# wifibasestation-tssop.net
KiCad netlist of a schematic drawn in EAGLE
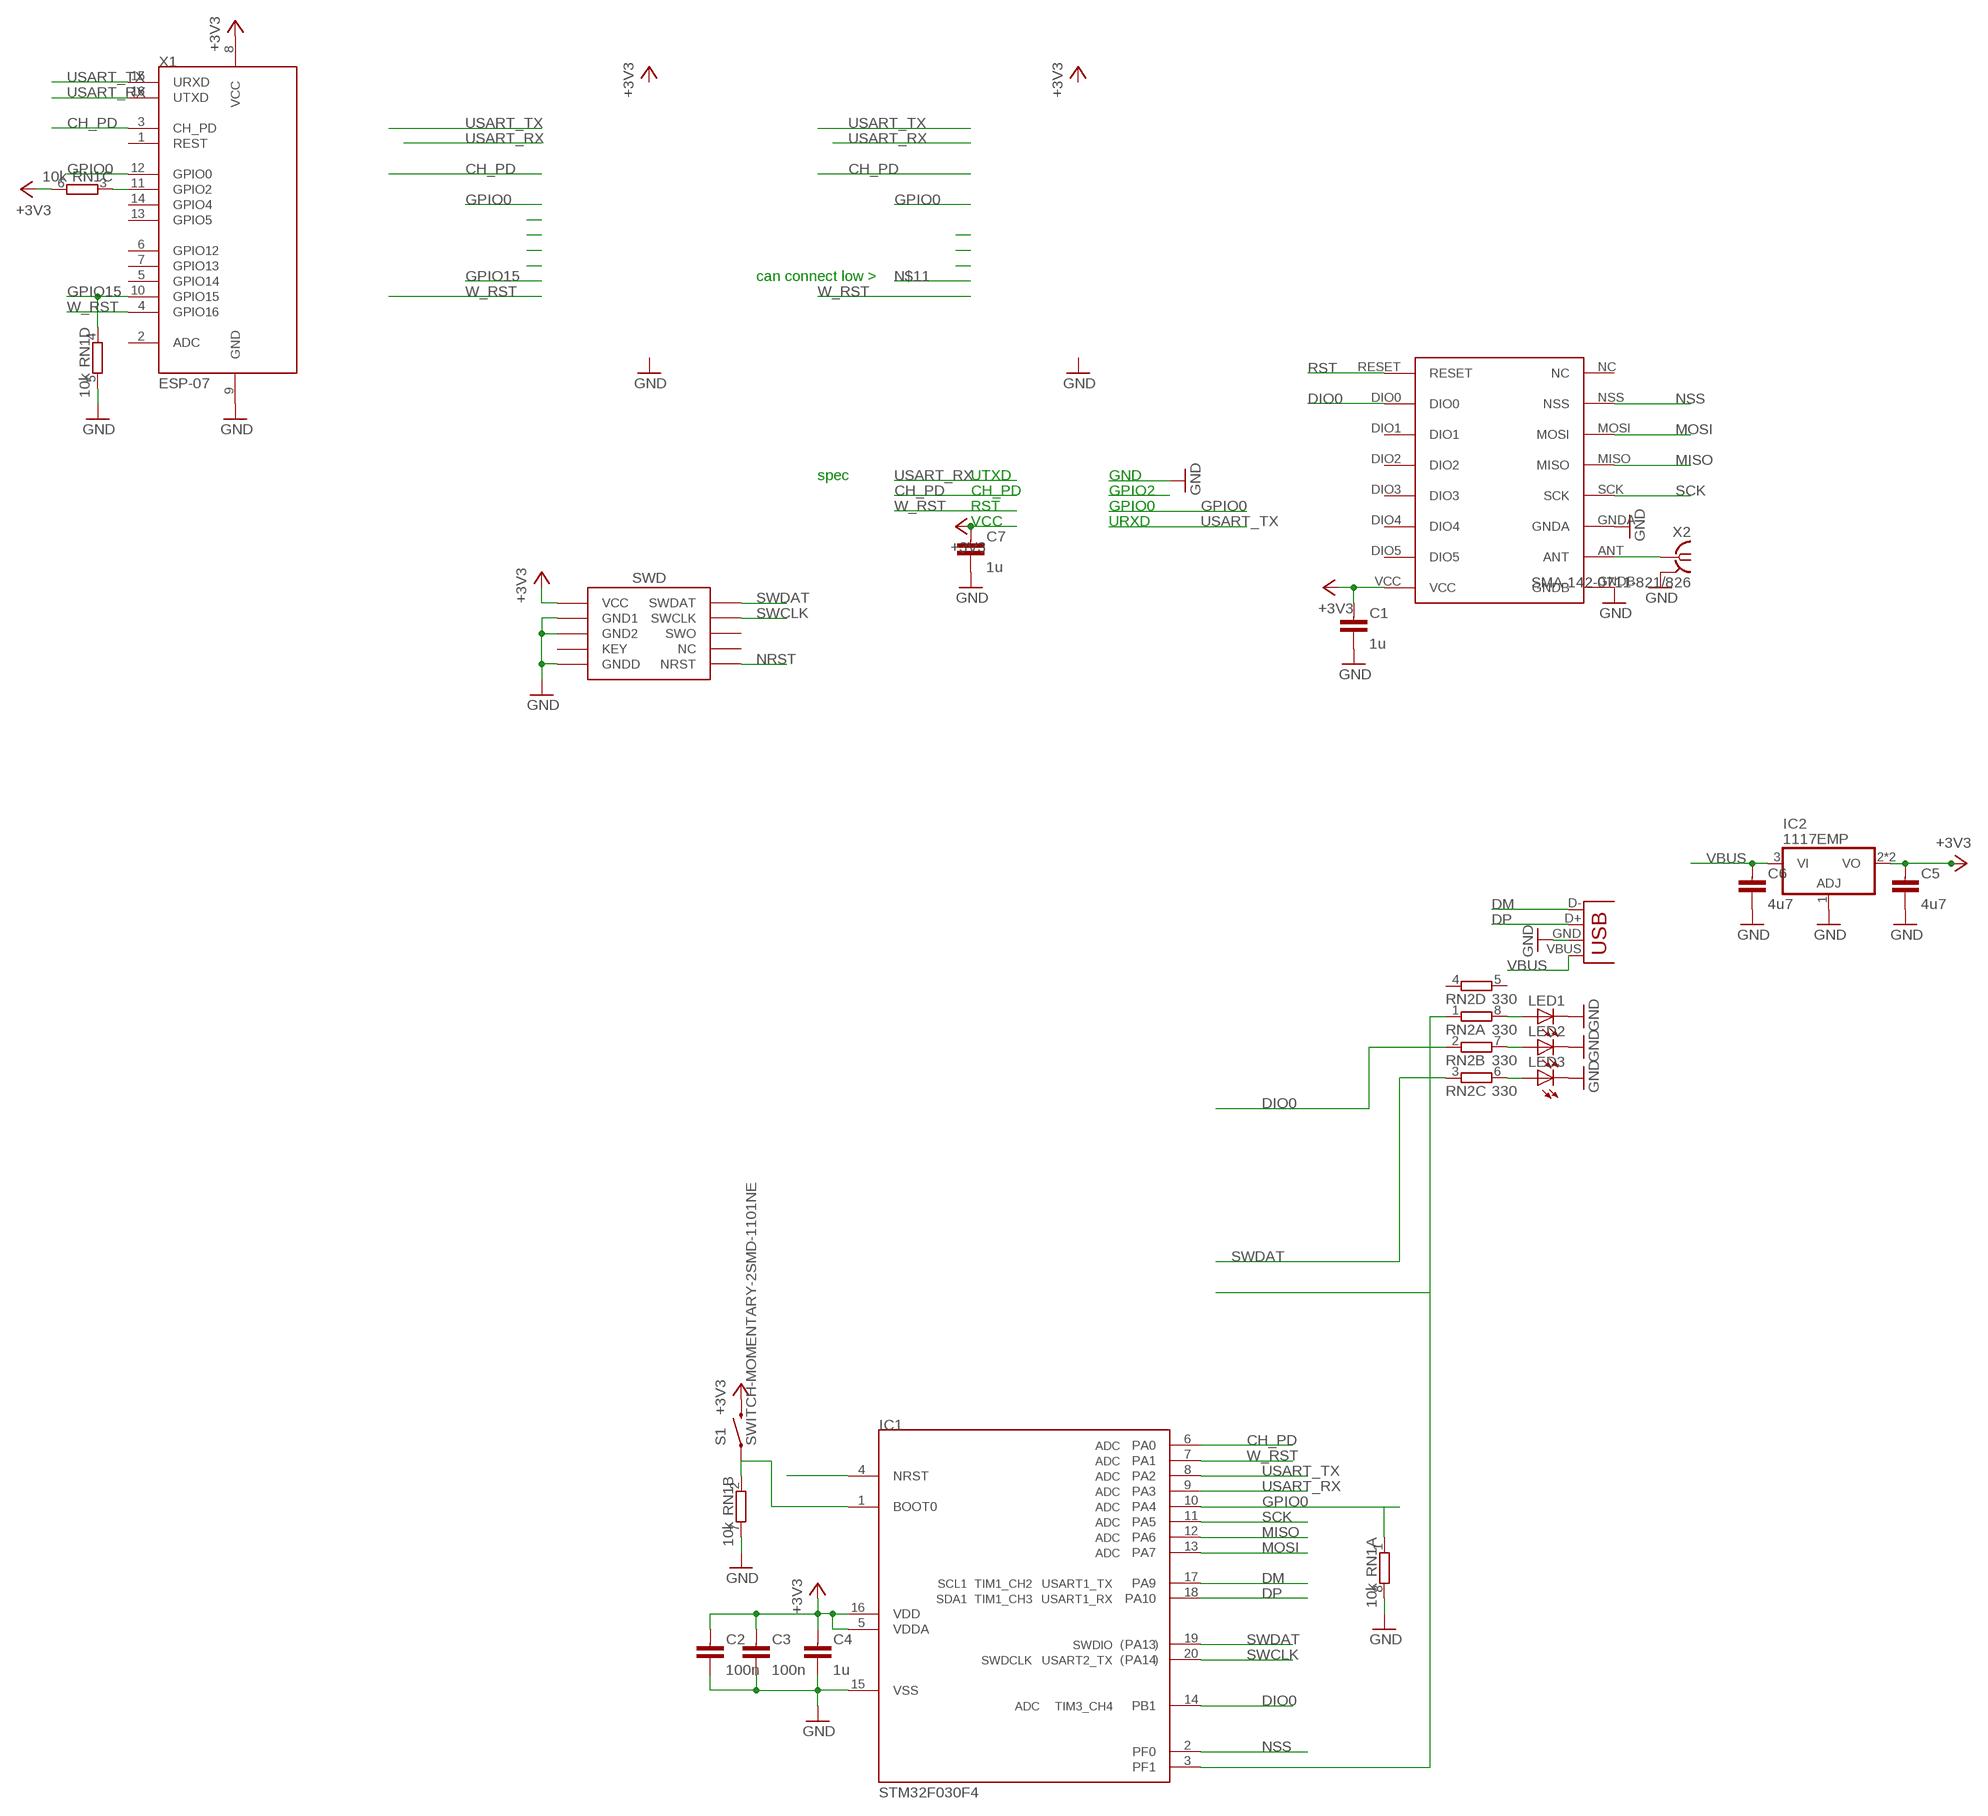
[diagram p0: schematic, sheet 1]

(export (version "E")
  (design (tool "Eeschema 10.0.6"))
  (components
    (comp (ref "C1")
      (value "1u")
      (footprint "eagle-import:C0603-N")
      (libsource (lib "eagle-import") (part "CAPACITOR0603-N"))
    )
    (comp (ref "C2")
      (value "100n")
      (footprint "eagle-import:C0603-N")
      (libsource (lib "eagle-import") (part "CAPACITOR0603-N"))
    )
    (comp (ref "C3")
      (value "100n")
      (footprint "eagle-import:C0603-N")
      (libsource (lib "eagle-import") (part "CAPACITOR0603-N"))
    )
    (comp (ref "C4")
      (value "1u")
      (footprint "eagle-import:C0603-N")
      (libsource (lib "eagle-import") (part "CAPACITOR0603-N"))
    )
    (comp (ref "C5")
      (value "4u7")
      (footprint "eagle-import:C0805-N")
      (libsource (lib "eagle-import") (part "CAPACITOR0805-N"))
    )
    (comp (ref "C6")
      (value "4u7")
      (footprint "eagle-import:C0603-N")
      (libsource (lib "eagle-import") (part "CAPACITOR0603-N"))
    )
    (comp (ref "C7")
      (value "1u")
      (footprint "eagle-import:C0603-N")
      (libsource (lib "eagle-import") (part "CAPACITOR0603-N"))
    )
    (comp (ref "IC1")
      (value "STM32F030F4")
      (footprint "eagle-import:TSSOP20")
      (libsource (lib "eagle-import") (part "STM32F030F4"))
    )
    (comp (ref "IC2")
      (value "1117EMP")
      (footprint "eagle-import:SOT223")
      (libsource (lib "eagle-import") (part "1117EMP"))
    )
    (comp (ref "J1")
      (value "SWD_SHROUD_SMD")
      (footprint "eagle-import:SWD_SMD_SHROUD")
      (libsource (lib "eagle-import") (part "SWD_SHROUD_SMD"))
    )
    (comp (ref "JP1")
      (value "USB-A-H")
      (footprint "eagle-import:USB-A-H")
      (libsource (lib "eagle-import") (part "USB-A-H"))
    )
    (comp (ref "LED1")
      (value "LEDCHIP-LED0805")
      (footprint "eagle-import:CHIP-LED0805")
      (libsource (lib "eagle-import") (part "LEDCHIP-LED0805"))
    )
    (comp (ref "LED2")
      (value "LEDCHIP-LED0805")
      (footprint "eagle-import:CHIP-LED0805")
      (libsource (lib "eagle-import") (part "LEDCHIP-LED0805"))
    )
    (comp (ref "LED3")
      (value "LEDCHIP-LED0805")
      (footprint "eagle-import:CHIP-LED0805")
      (libsource (lib "eagle-import") (part "LEDCHIP-LED0805"))
    )
    (comp (ref "RN1")
      (value "10k")
      (footprint "eagle-import:EXB38V")
      (libsource (lib "eagle-import") (part "4R-NEXB38V"))
    )
    (comp (ref "RN2")
      (value "330")
      (footprint "eagle-import:EXB38V")
      (libsource (lib "eagle-import") (part "4R-NEXB38V"))
    )
    (comp (ref "S1")
      (value "SWITCH-MOMENTARY-2SMD-1101NE")
      (footprint "eagle-import:TACTILE-SWITCH-1101NE")
      (libsource (lib "eagle-import") (part "SWITCH-MOMENTARY-2SMD-1101NE"))
    )
    (comp (ref "U$1")
      (value "RFM69HW")
      (footprint "eagle-import:RFM")
      (libsource (lib "eagle-import") (part "RFM69HW"))
    )
    (comp (ref "X1")
      (value "ESP-07")
      (footprint "eagle-import:ESP-07")
      (libsource (lib "eagle-import") (part "ESP-07"))
    )
    (comp (ref "X2")
      (value "SMA-142-0711-821/826")
      (footprint "eagle-import:J502-ND-142-0711-821_826")
      (fields (field (name "MF") "JOHNSON COMPONENTS") (field (name "MPN") "142-0711-821"))
      (libsource (lib "eagle-import") (part "SMA-142-0711-821/826"))
    )
  )
  (nets
    (net (code "1") (name "+3V3") (class "Default")
      (node (ref "C1") (pin "1") (pinfunction "1_1") (pintype "passive"))
      (node (ref "C2") (pin "1") (pinfunction "1_1") (pintype "passive"))
      (node (ref "C3") (pin "1") (pinfunction "1_1") (pintype "passive"))
      (node (ref "C4") (pin "1") (pinfunction "1_1") (pintype "passive"))
      (node (ref "C5") (pin "1") (pinfunction "1_1") (pintype "passive"))
      (node (ref "C7") (pin "1") (pinfunction "1_1") (pintype "passive"))
      (node (ref "IC1") (pin "16") (pinfunction "VDD_16") (pintype "power_in"))
      (node (ref "IC1") (pin "5") (pinfunction "VDDA_5") (pintype "power_in"))
      (node (ref "IC2") (pin "2") (pinfunction "VO_2") (pintype "passive"))
      (node (ref "IC2") (pin "4") (pinfunction "VO_4") (pintype "passive"))
      (node (ref "J1") (pin "1") (pinfunction "VCC_1") (pintype "power_in"))
      (node (ref "RN1") (pin "6") (pinfunction "2_6") (pintype "passive"))
      (node (ref "S1") (pin "2") (pinfunction "2_2") (pintype "passive"))
      (node (ref "U$1") (pin "VCC") (pinfunction "VCC_VCC") (pintype "bidirectional"))
      (node (ref "X1") (pin "8") (pinfunction "VCC_8") (pintype "power_in"))
    )
    (net (code "2") (name "/CH_PD") (class "Default")
      (node (ref "IC1") (pin "6") (pinfunction "PA0_6") (pintype "bidirectional"))
      (node (ref "X1") (pin "3") (pinfunction "CH_PD_3") (pintype "input"))
    )
    (net (code "3") (name "/DIO0") (class "Default")
      (node (ref "IC1") (pin "14") (pinfunction "PB1_14") (pintype "bidirectional"))
      (node (ref "RN2") (pin "2") (pinfunction "1_2") (pintype "passive"))
      (node (ref "U$1") (pin "DIO0") (pinfunction "DIO0_DIO0") (pintype "bidirectional"))
    )
    (net (code "4") (name "/DM") (class "Default")
      (node (ref "IC1") (pin "17") (pinfunction "PA9_17") (pintype "bidirectional"))
      (node (ref "JP1") (pin "D-") (pinfunction "D+_D-") (pintype "bidirectional"))
    )
    (net (code "5") (name "/DP") (class "Default")
      (node (ref "IC1") (pin "18") (pinfunction "PA10_18") (pintype "bidirectional"))
      (node (ref "JP1") (pin "D+") (pinfunction "D-_D+") (pintype "bidirectional"))
    )
    (net (code "6") (name "/GPIO0") (class "Default")
      (node (ref "IC1") (pin "10") (pinfunction "PA4_10") (pintype "bidirectional"))
      (node (ref "RN1") (pin "1") (pinfunction "1_1") (pintype "passive"))
      (node (ref "X1") (pin "12") (pinfunction "GPIO0_12") (pintype "bidirectional"))
    )
    (net (code "7") (name "/GPIO15") (class "Default")
      (node (ref "RN1") (pin "4") (pinfunction "1_4") (pintype "passive"))
      (node (ref "X1") (pin "10") (pinfunction "GPIO15_10") (pintype "bidirectional"))
    )
    (net (code "8") (name "/MISO") (class "Default")
      (node (ref "IC1") (pin "12") (pinfunction "PA6_12") (pintype "bidirectional"))
      (node (ref "U$1") (pin "MISO") (pinfunction "MISO_MISO") (pintype "bidirectional"))
    )
    (net (code "9") (name "/MOSI") (class "Default")
      (node (ref "IC1") (pin "13") (pinfunction "PA7_13") (pintype "bidirectional"))
      (node (ref "U$1") (pin "MOSI") (pinfunction "MOSI_MOSI") (pintype "bidirectional"))
    )
    (net (code "14") (name "/NRST") (class "Default")
      (node (ref "IC1") (pin "4") (pinfunction "NRST_4") (pintype "input"))
      (node (ref "J1") (pin "10") (pinfunction "NRST_10") (pintype "bidirectional"))
    )
    (net (code "15") (name "/NSS") (class "Default")
      (node (ref "IC1") (pin "2") (pinfunction "PF0_2") (pintype "bidirectional"))
      (node (ref "U$1") (pin "NSS") (pinfunction "NSS_NSS") (pintype "bidirectional"))
    )
    (net (code "16") (name "/RST") (class "Default")
      (node (ref "U$1") (pin "RESET") (pinfunction "RESET_RESET") (pintype "bidirectional"))
    )
    (net (code "17") (name "/SCK") (class "Default")
      (node (ref "IC1") (pin "11") (pinfunction "PA5_11") (pintype "bidirectional"))
      (node (ref "U$1") (pin "SCK") (pinfunction "SCK_SCK") (pintype "bidirectional"))
    )
    (net (code "18") (name "/SWCLK") (class "Default")
      (node (ref "IC1") (pin "20") (pinfunction "PA14_20") (pintype "bidirectional"))
      (node (ref "J1") (pin "4") (pinfunction "SWCLK_4") (pintype "bidirectional"))
    )
    (net (code "19") (name "/SWDAT") (class "Default")
      (node (ref "IC1") (pin "19") (pinfunction "PA13_19") (pintype "bidirectional"))
      (node (ref "J1") (pin "2") (pinfunction "SWDAT_2") (pintype "bidirectional"))
      (node (ref "RN2") (pin "3") (pinfunction "1_3") (pintype "passive"))
    )
    (net (code "20") (name "/USART_RX") (class "Default")
      (node (ref "IC1") (pin "9") (pinfunction "PA3_9") (pintype "bidirectional"))
      (node (ref "X1") (pin "16") (pinfunction "UTXD_16") (pintype "output"))
    )
    (net (code "21") (name "/USART_TX") (class "Default")
      (node (ref "IC1") (pin "8") (pinfunction "PA2_8") (pintype "bidirectional"))
      (node (ref "X1") (pin "15") (pinfunction "URXD_15") (pintype "input"))
    )
    (net (code "22") (name "/VBUS") (class "Default")
      (node (ref "C6") (pin "1") (pinfunction "1_1") (pintype "passive"))
      (node (ref "IC2") (pin "3") (pinfunction "VI_3") (pintype "input"))
      (node (ref "JP1") (pin "VBUS") (pinfunction "GND_VBUS") (pintype "bidirectional"))
    )
    (net (code "23") (name "/W_RST") (class "Default")
      (node (ref "IC1") (pin "7") (pinfunction "PA1_7") (pintype "bidirectional"))
      (node (ref "X1") (pin "4") (pinfunction "GPIO16_4") (pintype "bidirectional"))
    )
    (net (code "24") (name "GND") (class "Default")
      (node (ref "C1") (pin "2") (pinfunction "2_2") (pintype "passive"))
      (node (ref "C2") (pin "2") (pinfunction "2_2") (pintype "passive"))
      (node (ref "C3") (pin "2") (pinfunction "2_2") (pintype "passive"))
      (node (ref "C4") (pin "2") (pinfunction "2_2") (pintype "passive"))
      (node (ref "C5") (pin "2") (pinfunction "2_2") (pintype "passive"))
      (node (ref "C6") (pin "2") (pinfunction "2_2") (pintype "passive"))
      (node (ref "C7") (pin "2") (pinfunction "2_2") (pintype "passive"))
      (node (ref "IC1") (pin "15") (pinfunction "VSS_15") (pintype "power_in"))
      (node (ref "IC2") (pin "1") (pinfunction "ADJ_1") (pintype "input"))
      (node (ref "J1") (pin "3") (pinfunction "GND1_3") (pintype "power_in"))
      (node (ref "J1") (pin "5") (pinfunction "GND2_5") (pintype "power_in"))
      (node (ref "J1") (pin "9") (pinfunction "GNDD_9") (pintype "power_in"))
      (node (ref "JP1") (pin "GND") (pinfunction "VBUS_GND") (pintype "bidirectional"))
      (node (ref "LED1") (pin "C") (pinfunction "C_C") (pintype "passive"))
      (node (ref "LED2") (pin "C") (pinfunction "C_C") (pintype "passive"))
      (node (ref "LED3") (pin "C") (pinfunction "C_C") (pintype "passive"))
      (node (ref "RN1") (pin "5") (pinfunction "2_5") (pintype "passive"))
      (node (ref "RN1") (pin "7") (pinfunction "2_7") (pintype "passive"))
      (node (ref "RN1") (pin "8") (pinfunction "2_8") (pintype "passive"))
      (node (ref "U$1") (pin "GNDA") (pinfunction "GNDA_GNDA") (pintype "bidirectional"))
      (node (ref "U$1") (pin "GNDB") (pinfunction "GNDB_GNDB") (pintype "bidirectional"))
      (node (ref "X1") (pin "9") (pinfunction "GND_9") (pintype "power_in"))
      (node (ref "X2") (pin "G@1") (pinfunction "2_G@1") (pintype "passive"))
      (node (ref "X2") (pin "G@2") (pinfunction "2_G@2") (pintype "passive"))
      (node (ref "X2") (pin "G@3") (pinfunction "2_G@3") (pintype "passive"))
      (node (ref "X2") (pin "G@4") (pinfunction "2_G@4") (pintype "passive"))
    )
    (net (code "25") (name "Net-(IC1-BOOT0)") (class "Default")
      (node (ref "IC1") (pin "1") (pinfunction "BOOT0_1") (pintype "input"))
      (node (ref "RN1") (pin "2") (pinfunction "1_2") (pintype "passive"))
      (node (ref "S1") (pin "1") (pinfunction "1_1") (pintype "passive"))
    )
    (net (code "26") (name "Net-(IC1-PF1)") (class "Default")
      (node (ref "IC1") (pin "3") (pinfunction "PF1_3") (pintype "bidirectional"))
      (node (ref "RN2") (pin "1") (pinfunction "1_1") (pintype "passive"))
    )
    (net (code "27") (name "Net-(RN1C-1)") (class "Default")
      (node (ref "RN1") (pin "3") (pinfunction "1_3") (pintype "passive"))
      (node (ref "X1") (pin "11") (pinfunction "GPIO2_11") (pintype "bidirectional"))
    )
    (net (code "28") (name "Net-(RN2A-2)") (class "Default")
      (node (ref "LED1") (pin "A") (pinfunction "A_A") (pintype "passive"))
      (node (ref "RN2") (pin "8") (pinfunction "2_8") (pintype "passive"))
    )
    (net (code "29") (name "Net-(RN2B-2)") (class "Default")
      (node (ref "LED2") (pin "A") (pinfunction "A_A") (pintype "passive"))
      (node (ref "RN2") (pin "7") (pinfunction "2_7") (pintype "passive"))
    )
    (net (code "30") (name "Net-(RN2C-2)") (class "Default")
      (node (ref "LED3") (pin "A") (pinfunction "A_A") (pintype "passive"))
      (node (ref "RN2") (pin "6") (pinfunction "2_6") (pintype "passive"))
    )
    (net (code "31") (name "Net-(U$1-PadANT)") (class "Default")
      (node (ref "U$1") (pin "ANT") (pinfunction "ANT_ANT") (pintype "bidirectional"))
      (node (ref "X2") (pin "1") (pinfunction "1_1") (pintype "passive"))
    )
    (net (code "32") (name "unconnected-(J1-KEY-Pad7)") (class "Default")
      (node (ref "J1") (pin "7") (pinfunction "KEY_7") (pintype "bidirectional"))
    )
    (net (code "33") (name "unconnected-(J1-NC-Pad8)") (class "Default")
      (node (ref "J1") (pin "8") (pinfunction "NC_8") (pintype "no_connect"))
    )
    (net (code "34") (name "unconnected-(J1-SWO-Pad6)") (class "Default")
      (node (ref "J1") (pin "6") (pinfunction "SWO_6") (pintype "bidirectional"))
    )
    (net (code "35") (name "unconnected-(RN2D-1-Pad4)") (class "Default")
      (node (ref "RN2") (pin "4") (pinfunction "1_4") (pintype "passive"))
    )
    (net (code "36") (name "unconnected-(RN2D-2-Pad5)") (class "Default")
      (node (ref "RN2") (pin "5") (pinfunction "2_5") (pintype "passive"))
    )
    (net (code "37") (name "unconnected-(U$1-PadDIO1)") (class "Default")
      (node (ref "U$1") (pin "DIO1") (pinfunction "DIO1_DIO1") (pintype "bidirectional"))
    )
    (net (code "38") (name "unconnected-(U$1-PadDIO2)") (class "Default")
      (node (ref "U$1") (pin "DIO2") (pinfunction "DIO2_DIO2") (pintype "bidirectional"))
    )
    (net (code "39") (name "unconnected-(U$1-PadDIO3)") (class "Default")
      (node (ref "U$1") (pin "DIO3") (pinfunction "DIO3_DIO3") (pintype "bidirectional"))
    )
    (net (code "40") (name "unconnected-(U$1-PadDIO4)") (class "Default")
      (node (ref "U$1") (pin "DIO4") (pinfunction "DIO4_DIO4") (pintype "bidirectional"))
    )
    (net (code "41") (name "unconnected-(U$1-PadDIO5)") (class "Default")
      (node (ref "U$1") (pin "DIO5") (pinfunction "DIO5_DIO5") (pintype "bidirectional"))
    )
    (net (code "42") (name "unconnected-(U$1-PadNC)") (class "Default")
      (node (ref "U$1") (pin "NC") (pinfunction "NC_NC") (pintype "bidirectional"))
    )
    (net (code "43") (name "unconnected-(X1-ADC-Pad2)") (class "Default")
      (node (ref "X1") (pin "2") (pinfunction "ADC_2") (pintype "bidirectional"))
    )
    (net (code "44") (name "unconnected-(X1-GPIO4-Pad14)") (class "Default")
      (node (ref "X1") (pin "14") (pinfunction "GPIO4_14") (pintype "bidirectional"))
    )
    (net (code "45") (name "unconnected-(X1-GPIO5-Pad13)") (class "Default")
      (node (ref "X1") (pin "13") (pinfunction "GPIO5_13") (pintype "bidirectional"))
    )
    (net (code "46") (name "unconnected-(X1-GPIO12-Pad6)") (class "Default")
      (node (ref "X1") (pin "6") (pinfunction "GPIO12_6") (pintype "bidirectional"))
    )
    (net (code "47") (name "unconnected-(X1-GPIO13-Pad7)") (class "Default")
      (node (ref "X1") (pin "7") (pinfunction "GPIO13_7") (pintype "bidirectional"))
    )
    (net (code "48") (name "unconnected-(X1-GPIO14-Pad5)") (class "Default")
      (node (ref "X1") (pin "5") (pinfunction "GPIO14_5") (pintype "bidirectional"))
    )
    (net (code "49") (name "unconnected-(X1-REST-Pad1)") (class "Default")
      (node (ref "X1") (pin "1") (pinfunction "REST_1") (pintype "input"))
    )
  )
)
